# Protoboard.net
KiCad netlist of a schematic drawn in EAGLE
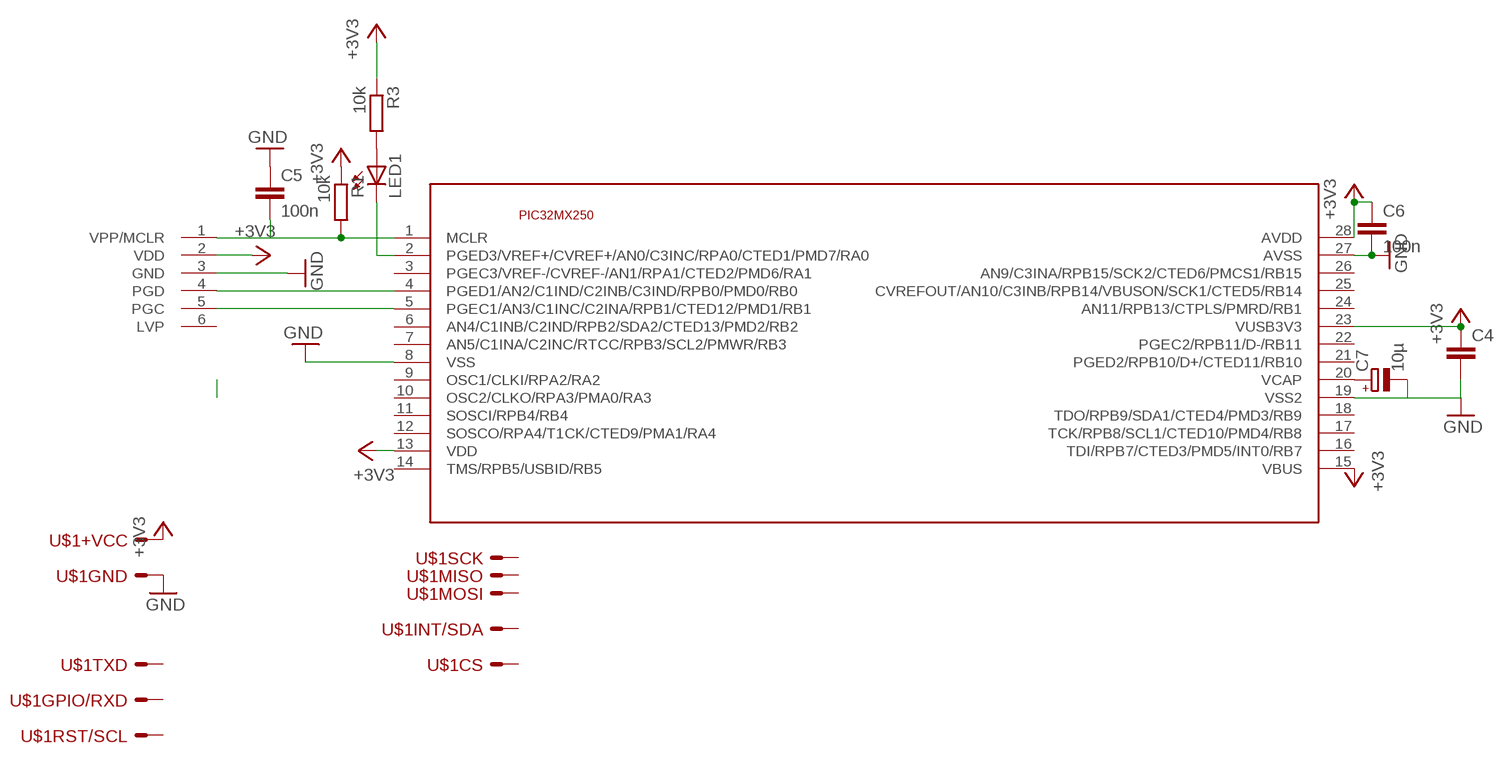
[diagram p0: schematic, sheet 1]

(export (version "E")
  (design (tool "Eeschema 10.0.6"))
  (components
    (comp (ref "C4")
      (value "C-EU050-025X075")
      (footprint "eagle-import:C050-025X075")
      (libsource (lib "eagle-import") (part "C-EU050-025X075"))
    )
    (comp (ref "C5")
      (value "100n")
      (footprint "eagle-import:C050-025X075")
      (libsource (lib "eagle-import") (part "C-EU050-025X075"))
    )
    (comp (ref "C6")
      (value "100n")
      (footprint "eagle-import:C050-024X044")
      (libsource (lib "eagle-import") (part "C-EU050-024X044"))
    )
    (comp (ref "C7")
      (value "10µ")
      (footprint "eagle-import:E1,8-4")
      (libsource (lib "eagle-import") (part "CPOL-EUE1.8-4"))
    )
    (comp (ref "LED1")
      (value "LED5MM")
      (footprint "eagle-import:LED5MM")
      (libsource (lib "eagle-import") (part "LED5MM"))
    )
    (comp (ref "R1")
      (value "10k")
      (footprint "eagle-import:0207_10")
      (libsource (lib "eagle-import") (part "R-EU_0207/10"))
    )
    (comp (ref "R3")
      (value "10k")
      (footprint "eagle-import:0207_10")
      (libsource (lib "eagle-import") (part "R-EU_0207/10"))
    )
    (comp (ref "U$1")
      (value "SPI_BUS2")
      (footprint "eagle-import:SPI_BUS2")
      (libsource (lib "eagle-import") (part "SPI_BUS2"))
    )
    (comp (ref "U$2")
      (value "ICSP-6_6P")
      (footprint "eagle-import:1X06-CLEANBIG")
      (libsource (lib "eagle-import") (part "ICSP-6_6P"))
    )
    (comp (ref "U$3")
      (value "PIC32MX2XXSOIC")
      (footprint "eagle-import:SOIC28")
      (libsource (lib "eagle-import") (part "PIC32MX2XXSOIC"))
    )
  )
  (nets
    (net (code "1") (name "+3V3") (class "Default")
      (node (ref "C4") (pin "1") (pinfunction "1_1") (pintype "passive"))
      (node (ref "C6") (pin "1") (pinfunction "1_1") (pintype "passive"))
      (node (ref "R1") (pin "1") (pinfunction "1_1") (pintype "passive"))
      (node (ref "R3") (pin "1") (pinfunction "1_1") (pintype "passive"))
      (node (ref "U$1") (pin "+VCC") (pinfunction "S_+VCC") (pintype "passive"))
      (node (ref "U$2") (pin "2") (pinfunction "VDD_2") (pintype "bidirectional"))
      (node (ref "U$3") (pin "13") (pinfunction "VDD_13") (pintype "power_in"))
      (node (ref "U$3") (pin "15") (pinfunction "VBUS_15") (pintype "bidirectional"))
      (node (ref "U$3") (pin "23") (pinfunction "VUSB3V3_23") (pintype "bidirectional"))
      (node (ref "U$3") (pin "28") (pinfunction "AVDD_28") (pintype "bidirectional"))
    )
    (net (code "2") (name "GND") (class "Default")
      (node (ref "C4") (pin "2") (pinfunction "2_2") (pintype "passive"))
      (node (ref "C5") (pin "1") (pinfunction "1_1") (pintype "passive"))
      (node (ref "C6") (pin "2") (pinfunction "2_2") (pintype "passive"))
      (node (ref "C7") (pin "-") (pinfunction "-_-") (pintype "passive"))
      (node (ref "U$1") (pin "GND") (pinfunction "S_GND") (pintype "passive"))
      (node (ref "U$2") (pin "3") (pinfunction "GND_3") (pintype "bidirectional"))
      (node (ref "U$3") (pin "19") (pinfunction "VSS2_19") (pintype "bidirectional"))
      (node (ref "U$3") (pin "27") (pinfunction "AVSS_27") (pintype "bidirectional"))
      (node (ref "U$3") (pin "8") (pinfunction "VSS_8") (pintype "power_in"))
    )
    (net (code "3") (name "Net-(LED1-C)") (class "Default")
      (node (ref "LED1") (pin "K") (pinfunction "C_K") (pintype "passive"))
      (node (ref "U$3") (pin "2") (pinfunction "PGED3/VREF+/CVREF+/AN0/C3INC/RPA0/CTED1/PMD7/RA0_2") (pintype "bidirectional"))
    )
    (net (code "4") (name "Net-(LED1-PadA)") (class "Default")
      (node (ref "LED1") (pin "A") (pinfunction "A_A") (pintype "passive"))
      (node (ref "R3") (pin "2") (pinfunction "2_2") (pintype "passive"))
    )
    (net (code "5") (name "Net-(U$2-PGC)") (class "Default")
      (node (ref "U$2") (pin "5") (pinfunction "PGC_5") (pintype "bidirectional"))
      (node (ref "U$3") (pin "5") (pinfunction "PGEC1/AN3/C1INC/C2INA/RPB1/CTED12/PMD1/RB1_5") (pintype "bidirectional"))
    )
    (net (code "6") (name "Net-(U$2-PGD)") (class "Default")
      (node (ref "U$2") (pin "4") (pinfunction "PGD_4") (pintype "bidirectional"))
      (node (ref "U$3") (pin "4") (pinfunction "PGED1/AN2/C1IND/C2INB/C3IND/RPB0/PMD0/RB0_4") (pintype "bidirectional"))
    )
    (net (code "7") (name "Net-(U$2-VPP{slash}MCLR)") (class "Default")
      (node (ref "C5") (pin "2") (pinfunction "2_2") (pintype "passive"))
      (node (ref "R1") (pin "2") (pinfunction "2_2") (pintype "passive"))
      (node (ref "U$2") (pin "1") (pinfunction "VPP/MCLR_1") (pintype "bidirectional"))
      (node (ref "U$3") (pin "1") (pinfunction "MCLR_1") (pintype "bidirectional"))
    )
    (net (code "8") (name "Net-(U$3-VCAP)") (class "Default")
      (node (ref "C7") (pin "+") (pinfunction "+_+") (pintype "passive"))
      (node (ref "U$3") (pin "20") (pinfunction "VCAP_20") (pintype "bidirectional"))
    )
    (net (code "9") (name "unconnected-(U$1B-S-PadCS)") (class "Default")
      (node (ref "U$1") (pin "CS") (pinfunction "S_CS") (pintype "passive"))
    )
    (net (code "10") (name "unconnected-(U$1D-S-PadGPIO{slash}RXD)") (class "Default")
      (node (ref "U$1") (pin "GPIO/RXD") (pinfunction "S_GPIO/RXD") (pintype "passive"))
    )
    (net (code "11") (name "unconnected-(U$1E-S-PadINT{slash}SDA)") (class "Default")
      (node (ref "U$1") (pin "INT/SDA") (pinfunction "S_INT/SDA") (pintype "passive"))
    )
    (net (code "12") (name "unconnected-(U$1F-S-PadMISO)") (class "Default")
      (node (ref "U$1") (pin "MISO") (pinfunction "S_MISO") (pintype "passive"))
    )
    (net (code "13") (name "unconnected-(U$1G-S-PadMOSI)") (class "Default")
      (node (ref "U$1") (pin "MOSI") (pinfunction "S_MOSI") (pintype "passive"))
    )
    (net (code "14") (name "unconnected-(U$1H-S-PadRST{slash}SCL)") (class "Default")
      (node (ref "U$1") (pin "RST/SCL") (pinfunction "S_RST/SCL") (pintype "passive"))
    )
    (net (code "15") (name "unconnected-(U$1I-S-PadSCK)") (class "Default")
      (node (ref "U$1") (pin "SCK") (pinfunction "S_SCK") (pintype "passive"))
    )
    (net (code "16") (name "unconnected-(U$1J-S-PadTXD)") (class "Default")
      (node (ref "U$1") (pin "TXD") (pinfunction "S_TXD") (pintype "passive"))
    )
    (net (code "17") (name "unconnected-(U$2-LVP-Pad6)") (class "Default")
      (node (ref "U$2") (pin "6") (pinfunction "LVP_6") (pintype "bidirectional"))
    )
    (net (code "18") (name "unconnected-(U$3-AN4{slash}C1INB{slash}C2IND{slash}RPB2{slash}SDA2{slash}CTED13{slash}PMD2{slash}RB2-Pad6)") (class "Default")
      (node (ref "U$3") (pin "6") (pinfunction "AN4/C1INB/C2IND/RPB2/SDA2/CTED13/PMD2/RB2_6") (pintype "bidirectional"))
    )
    (net (code "19") (name "unconnected-(U$3-AN5{slash}C1INA{slash}C2INC{slash}RTCC{slash}RPB3{slash}SCL2{slash}PMWR{slash}RB3-Pad7)") (class "Default")
      (node (ref "U$3") (pin "7") (pinfunction "AN5/C1INA/C2INC/RTCC/RPB3/SCL2/PMWR/RB3_7") (pintype "bidirectional"))
    )
    (net (code "20") (name "unconnected-(U$3-AN9{slash}C3INA{slash}RPB15{slash}SCK2{slash}CTED6{slash}PMCS1{slash}RB15-Pad26)") (class "Default")
      (node (ref "U$3") (pin "26") (pinfunction "AN9/C3INA/RPB15/SCK2/CTED6/PMCS1/RB15_26") (pintype "bidirectional"))
    )
    (net (code "21") (name "unconnected-(U$3-AN11{slash}RPB13{slash}CTPLS{slash}PMRD{slash}RB1-Pad24)") (class "Default")
      (node (ref "U$3") (pin "24") (pinfunction "AN11/RPB13/CTPLS/PMRD/RB1_24") (pintype "bidirectional"))
    )
    (net (code "22") (name "unconnected-(U$3-CVREFOUT{slash}AN10{slash}C3INB{slash}RPB14{slash}VBUSON{slash}SCK1{slash}CTED5{slash}RB14-Pad25)") (class "Default")
      (node (ref "U$3") (pin "25") (pinfunction "CVREFOUT/AN10/C3INB/RPB14/VBUSON/SCK1/CTED5/RB14_25") (pintype "bidirectional"))
    )
    (net (code "23") (name "unconnected-(U$3-OSC1{slash}CLKI{slash}RPA2{slash}RA2-Pad9)") (class "Default")
      (node (ref "U$3") (pin "9") (pinfunction "OSC1/CLKI/RPA2/RA2_9") (pintype "bidirectional"))
    )
    (net (code "24") (name "unconnected-(U$3-OSC2{slash}CLKO{slash}RPA3{slash}PMA0{slash}RA3-Pad10)") (class "Default")
      (node (ref "U$3") (pin "10") (pinfunction "OSC2/CLKO/RPA3/PMA0/RA3_10") (pintype "bidirectional"))
    )
    (net (code "25") (name "unconnected-(U$3-PGEC2{slash}RPB11{slash}D-{slash}RB11-Pad22)") (class "Default")
      (node (ref "U$3") (pin "22") (pinfunction "PGEC2/RPB11/D-/RB11_22") (pintype "bidirectional"))
    )
    (net (code "26") (name "unconnected-(U$3-PGEC3{slash}VREF-{slash}CVREF-{slash}AN1{slash}RPA1{slash}CTED2{slash}PMD6{slash}RA1-Pad3)") (class "Default")
      (node (ref "U$3") (pin "3") (pinfunction "PGEC3/VREF-/CVREF-/AN1/RPA1/CTED2/PMD6/RA1_3") (pintype "bidirectional"))
    )
    (net (code "27") (name "unconnected-(U$3-PGED2{slash}RPB10{slash}D+{slash}CTED11{slash}RB10-Pad21)") (class "Default")
      (node (ref "U$3") (pin "21") (pinfunction "PGED2/RPB10/D+/CTED11/RB10_21") (pintype "bidirectional"))
    )
    (net (code "28") (name "unconnected-(U$3-SOSCI{slash}RPB4{slash}RB4-Pad11)") (class "Default")
      (node (ref "U$3") (pin "11") (pinfunction "SOSCI/RPB4/RB4_11") (pintype "bidirectional"))
    )
    (net (code "29") (name "unconnected-(U$3-SOSCO{slash}RPA4{slash}T1CK{slash}CTED9{slash}PMA1{slash}RA4-Pad12)") (class "Default")
      (node (ref "U$3") (pin "12") (pinfunction "SOSCO/RPA4/T1CK/CTED9/PMA1/RA4_12") (pintype "bidirectional"))
    )
    (net (code "30") (name "unconnected-(U$3-TCK{slash}RPB8{slash}SCL1{slash}CTED10{slash}PMD4{slash}RB8-Pad17)") (class "Default")
      (node (ref "U$3") (pin "17") (pinfunction "TCK/RPB8/SCL1/CTED10/PMD4/RB8_17") (pintype "bidirectional"))
    )
    (net (code "31") (name "unconnected-(U$3-TDI{slash}RPB7{slash}CTED3{slash}PMD5{slash}INT0{slash}RB7-Pad16)") (class "Default")
      (node (ref "U$3") (pin "16") (pinfunction "TDI/RPB7/CTED3/PMD5/INT0/RB7_16") (pintype "bidirectional"))
    )
    (net (code "32") (name "unconnected-(U$3-TDO{slash}RPB9{slash}SDA1{slash}CTED4{slash}PMD3{slash}RB9-Pad18)") (class "Default")
      (node (ref "U$3") (pin "18") (pinfunction "TDO/RPB9/SDA1/CTED4/PMD3/RB9_18") (pintype "bidirectional"))
    )
    (net (code "33") (name "unconnected-(U$3-TMS{slash}RPB5{slash}USBID{slash}RB5-Pad14)") (class "Default")
      (node (ref "U$3") (pin "14") (pinfunction "TMS/RPB5/USBID/RB5_14") (pintype "bidirectional"))
    )
  )
)
